# QCopterMV_FFC_Sch.net
KiCad netlist of a schematic drawn in Altium Designer
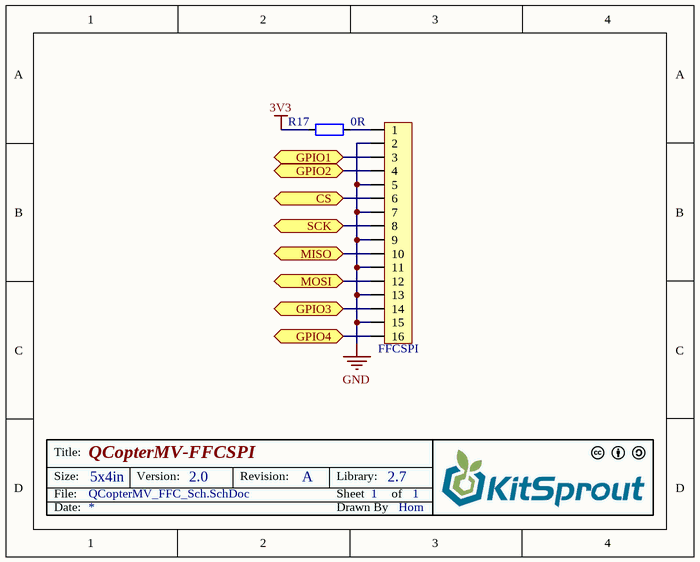
[diagram p0: QCopterMV_FFC_Sch.SchDoc]

(export (version "E")
  (design (tool "Eeschema 10.0.6"))
  (components
    (comp (ref "FFCSPI")
      (value "FFC_0.5_16")
      (footprint "PCB_ConnectorFFC:FFC_0.5_16")
      (description "FFC")
      (libsource (lib "SCH_Connector") (part "FFC_0.5_16"))
    )
    (comp (ref "R17")
      (value "0R")
      (footprint "PCB_PassiveRes:RES_0603")
      (description "Resistor")
      (fields (field (name "Comment") "Res_0603"))
      (libsource (lib "SCH_Passive") (part "Res_0603"))
    )
  )
  (nets
    (net (code "1") (name "/CS") (class "Default")
      (node (ref "FFCSPI") (pin "6") (pinfunction "6_6") (pintype "passive"))
    )
    (net (code "2") (name "/GPIO1") (class "Default")
      (node (ref "FFCSPI") (pin "3") (pinfunction "3_3") (pintype "passive"))
    )
    (net (code "3") (name "/GPIO2") (class "Default")
      (node (ref "FFCSPI") (pin "4") (pinfunction "4_4") (pintype "passive"))
    )
    (net (code "4") (name "/GPIO3") (class "Default")
      (node (ref "FFCSPI") (pin "14") (pinfunction "14_14") (pintype "passive"))
    )
    (net (code "5") (name "/GPIO4") (class "Default")
      (node (ref "FFCSPI") (pin "16") (pinfunction "16_16") (pintype "passive"))
    )
    (net (code "6") (name "/MISO") (class "Default")
      (node (ref "FFCSPI") (pin "10") (pinfunction "10_10") (pintype "passive"))
    )
    (net (code "7") (name "/MOSI") (class "Default")
      (node (ref "FFCSPI") (pin "12") (pinfunction "12_12") (pintype "passive"))
    )
    (net (code "8") (name "/SCK") (class "Default")
      (node (ref "FFCSPI") (pin "8") (pinfunction "8_8") (pintype "passive"))
    )
    (net (code "9") (name "3V3") (class "Default")
      (node (ref "R17") (pin "1") (pinfunction "1_1") (pintype "passive"))
    )
    (net (code "10") (name "GND") (class "Default")
      (node (ref "FFCSPI") (pin "11") (pinfunction "11_11") (pintype "passive"))
      (node (ref "FFCSPI") (pin "13") (pinfunction "13_13") (pintype "passive"))
      (node (ref "FFCSPI") (pin "15") (pinfunction "15_15") (pintype "passive"))
      (node (ref "FFCSPI") (pin "2") (pinfunction "2_2") (pintype "passive"))
      (node (ref "FFCSPI") (pin "5") (pinfunction "5_5") (pintype "passive"))
      (node (ref "FFCSPI") (pin "7") (pinfunction "7_7") (pintype "passive"))
      (node (ref "FFCSPI") (pin "9") (pinfunction "9_9") (pintype "passive"))
    )
    (net (code "11") (name "Net-(FFCSPI-Pad1)") (class "Default")
      (node (ref "FFCSPI") (pin "1") (pinfunction "1_1") (pintype "passive"))
      (node (ref "R17") (pin "2") (pinfunction "2_2") (pintype "passive"))
    )
  )
)
